# rev0_1.net
KiCad netlist of a schematic drawn in EAGLE
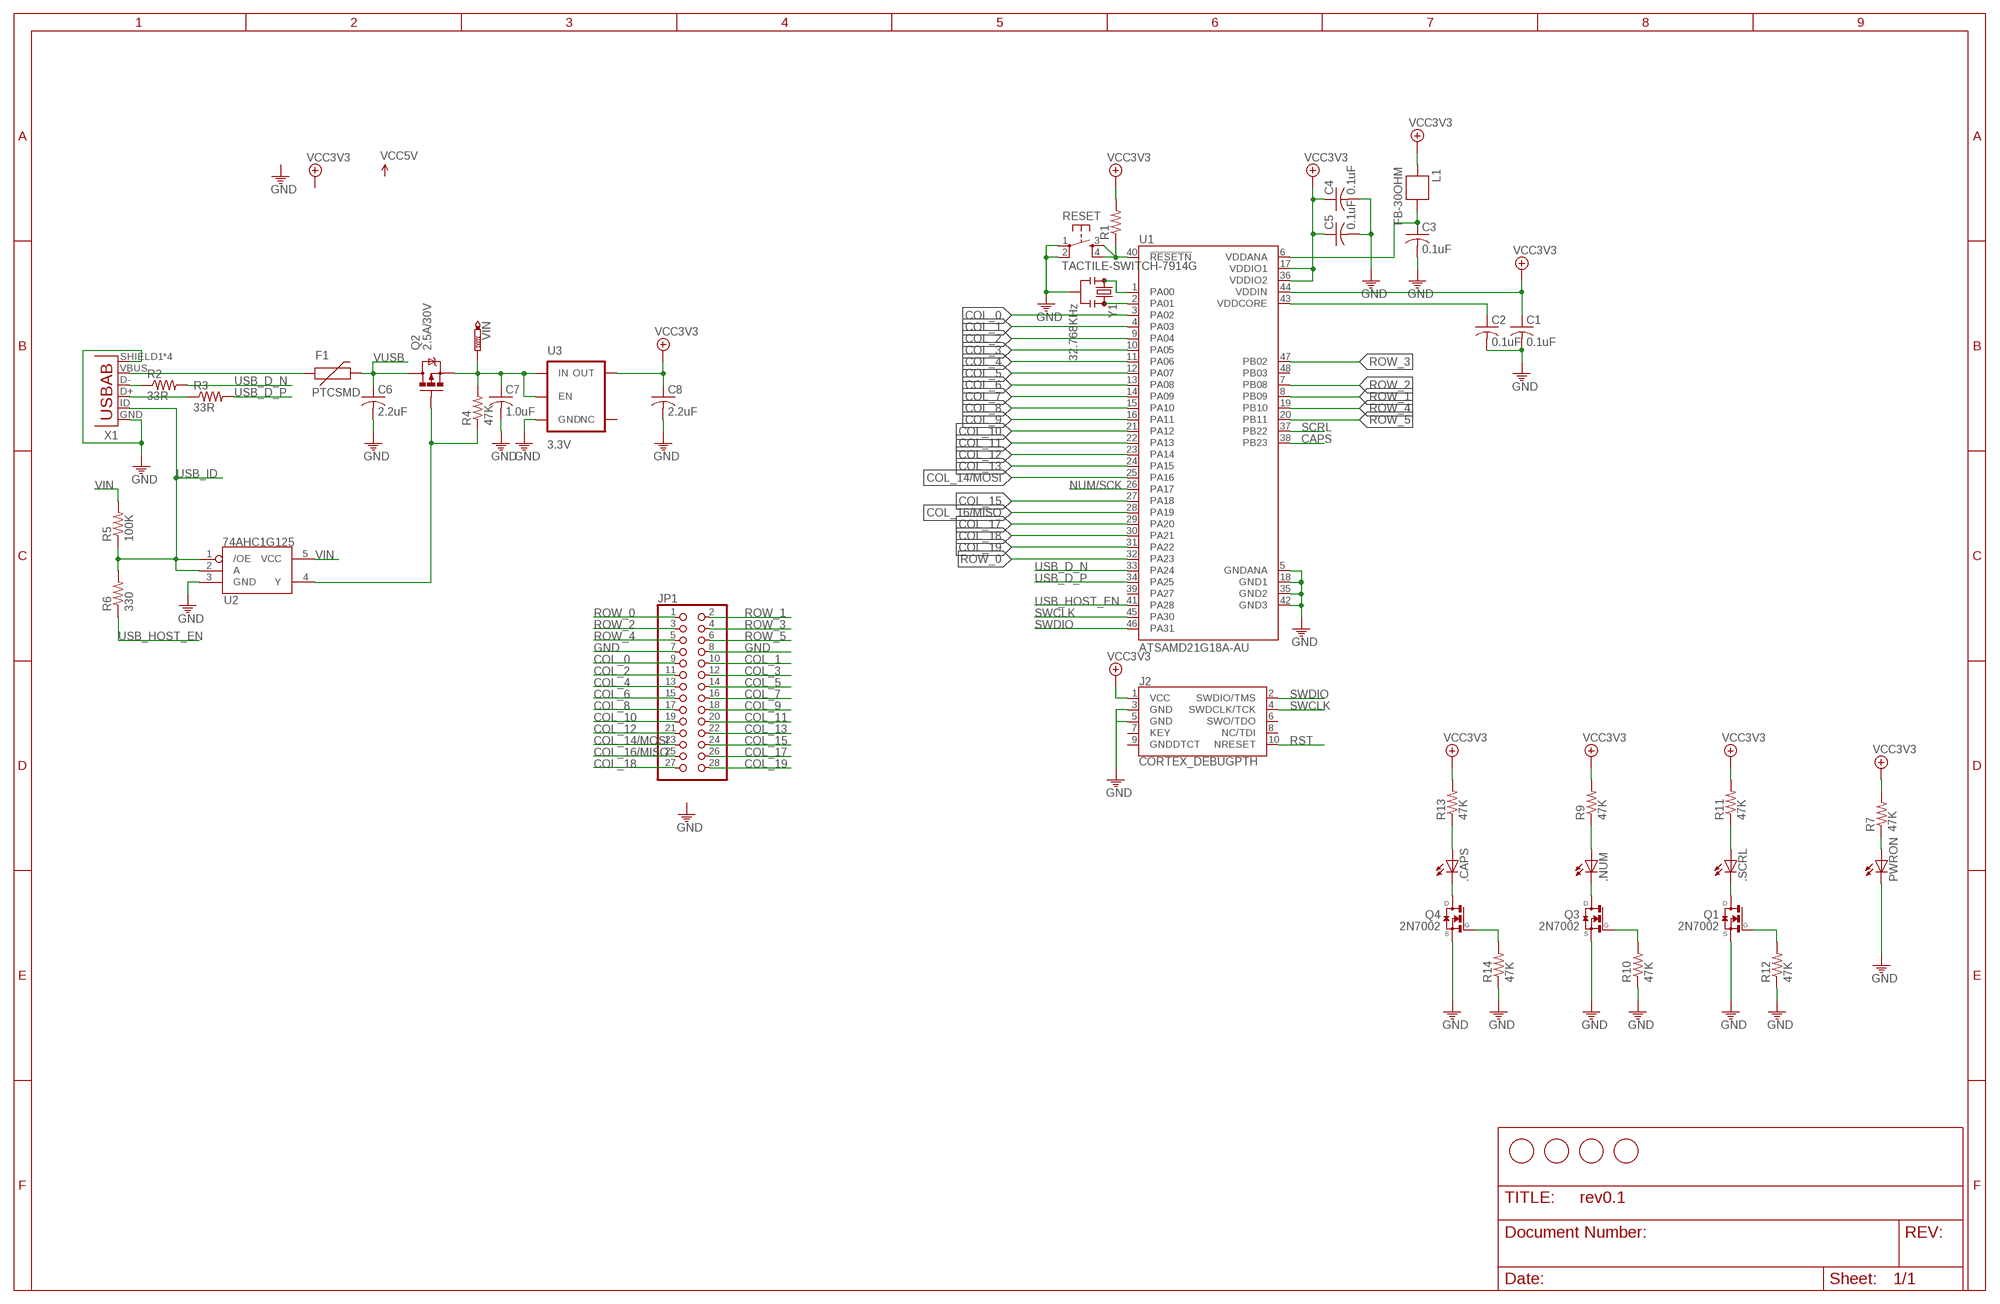
[diagram p0: schematic, sheet 1]

(export (version "E")
  (design (tool "Eeschema 10.0.6"))
  (components
    (comp (ref ".CAPS")
      (value "LEDCHIPLED_1206")
      (footprint "eagle-import:CHIPLED_1206")
      (libsource (lib "eagle-import") (part "LEDCHIPLED_1206"))
    )
    (comp (ref ".NUM")
      (value "LEDCHIPLED_1206")
      (footprint "eagle-import:CHIPLED_1206")
      (libsource (lib "eagle-import") (part "LEDCHIPLED_1206"))
    )
    (comp (ref ".SCRL")
      (value "LEDCHIPLED_1206")
      (footprint "eagle-import:CHIPLED_1206")
      (libsource (lib "eagle-import") (part "LEDCHIPLED_1206"))
    )
    (comp (ref "C1")
      (value "0.1uF")
      (footprint "eagle-import:C0603")
      (libsource (lib "eagle-import") (part "C-USC0603"))
    )
    (comp (ref "C2")
      (value "0.1uF")
      (footprint "eagle-import:C0603")
      (libsource (lib "eagle-import") (part "C-USC0603"))
    )
    (comp (ref "C3")
      (value "0.1uF")
      (footprint "eagle-import:C0603")
      (libsource (lib "eagle-import") (part "C-USC0603"))
    )
    (comp (ref "C4")
      (value "0.1uF")
      (footprint "eagle-import:C0603")
      (libsource (lib "eagle-import") (part "C-USC0603"))
    )
    (comp (ref "C5")
      (value "0.1uF")
      (footprint "eagle-import:C0603")
      (libsource (lib "eagle-import") (part "C-USC0603"))
    )
    (comp (ref "C6")
      (value "2.2uF")
      (footprint "eagle-import:C0603")
      (libsource (lib "eagle-import") (part "C-USC0603"))
    )
    (comp (ref "C7")
      (value "1.0uF")
      (footprint "eagle-import:C0603")
      (libsource (lib "eagle-import") (part "C-USC0603"))
    )
    (comp (ref "C8")
      (value "2.2uF")
      (footprint "eagle-import:C0603")
      (libsource (lib "eagle-import") (part "C-USC0603"))
    )
    (comp (ref "F1")
      (value "PTCSMD")
      (footprint "eagle-import:PTC-1206")
      (libsource (lib "eagle-import") (part "PTCSMD"))
    )
    (comp (ref "J2")
      (value "CORTEX_DEBUGPTH")
      (footprint "eagle-import:2X5-PTH-1.27MM")
      (libsource (lib "eagle-import") (part "CORTEX_DEBUGPTH"))
    )
    (comp (ref "JP1")
      (value "PINHD-2X14-CB")
      (footprint "eagle-import:2X14-CLEANBIG")
      (libsource (lib "eagle-import") (part "PINHD-2X14-CB"))
    )
    (comp (ref "L1")
      (value "FB-30OHM")
      (footprint "eagle-import:0603")
      (libsource (lib "eagle-import") (part "FB"))
    )
    (comp (ref "PWRON")
      (value "LEDCHIPLED_1206")
      (footprint "eagle-import:CHIPLED_1206")
      (libsource (lib "eagle-import") (part "LEDCHIPLED_1206"))
    )
    (comp (ref "Q1")
      (value "2N7002")
      (footprint "eagle-import:SOT23")
      (libsource (lib "eagle-import") (part "2N7002"))
    )
    (comp (ref "Q2")
      (value "2.5A/30V")
      (footprint "eagle-import:SOT23-3")
      (libsource (lib "eagle-import") (part "MOSFET-PCHANNELDMG2307L"))
    )
    (comp (ref "Q3")
      (value "2N7002")
      (footprint "eagle-import:SOT23")
      (libsource (lib "eagle-import") (part "2N7002"))
    )
    (comp (ref "Q4")
      (value "2N7002")
      (footprint "eagle-import:SOT23")
      (libsource (lib "eagle-import") (part "2N7002"))
    )
    (comp (ref "R1")
      (value "R-US_R0603")
      (footprint "eagle-import:R0603")
      (libsource (lib "eagle-import") (part "R-US_R0603"))
    )
    (comp (ref "R2")
      (value "33R")
      (footprint "eagle-import:R0603")
      (libsource (lib "eagle-import") (part "R-US_R0603"))
    )
    (comp (ref "R3")
      (value "33R")
      (footprint "eagle-import:R0603")
      (libsource (lib "eagle-import") (part "R-US_R0603"))
    )
    (comp (ref "R4")
      (value "47K")
      (footprint "eagle-import:R0603")
      (libsource (lib "eagle-import") (part "R-US_R0603"))
    )
    (comp (ref "R5")
      (value "100K")
      (footprint "eagle-import:R0603")
      (libsource (lib "eagle-import") (part "R-US_R0603"))
    )
    (comp (ref "R6")
      (value "330")
      (footprint "eagle-import:R0603")
      (libsource (lib "eagle-import") (part "R-US_R0603"))
    )
    (comp (ref "R7")
      (value "47K")
      (footprint "eagle-import:R0603")
      (libsource (lib "eagle-import") (part "R-US_R0603"))
    )
    (comp (ref "R9")
      (value "47K")
      (footprint "eagle-import:R0603")
      (libsource (lib "eagle-import") (part "R-US_R0603"))
    )
    (comp (ref "R10")
      (value "47K")
      (footprint "eagle-import:R0603")
      (libsource (lib "eagle-import") (part "R-US_R0603"))
    )
    (comp (ref "R11")
      (value "47K")
      (footprint "eagle-import:R0603")
      (libsource (lib "eagle-import") (part "R-US_R0603"))
    )
    (comp (ref "R12")
      (value "47K")
      (footprint "eagle-import:R0603")
      (libsource (lib "eagle-import") (part "R-US_R0603"))
    )
    (comp (ref "R13")
      (value "47K")
      (footprint "eagle-import:R0603")
      (libsource (lib "eagle-import") (part "R-US_R0603"))
    )
    (comp (ref "R14")
      (value "47K")
      (footprint "eagle-import:R0603")
      (libsource (lib "eagle-import") (part "R-US_R0603"))
    )
    (comp (ref "RESET")
      (value "TACTILE-SWITCH-7914G")
      (footprint "eagle-import:7914G")
      (libsource (lib "eagle-import") (part "TACTILE-SWITCH-7914G"))
    )
    (comp (ref "U$6")
      (value "FIDUCIAL")
      (footprint "eagle-import:FIDUCIAL_1MM")
      (libsource (lib "eagle-import") (part "FIDUCIAL"))
    )
    (comp (ref "U$19")
      (value "FIDUCIAL")
      (footprint "eagle-import:FIDUCIAL_1MM")
      (libsource (lib "eagle-import") (part "FIDUCIAL"))
    )
    (comp (ref "U$20")
      (value "FIDUCIAL")
      (footprint "eagle-import:FIDUCIAL_1MM")
      (libsource (lib "eagle-import") (part "FIDUCIAL"))
    )
    (comp (ref "U$21")
      (value "FIDUCIAL")
      (footprint "eagle-import:FIDUCIAL_1MM")
      (libsource (lib "eagle-import") (part "FIDUCIAL"))
    )
    (comp (ref "U1")
      (value "ATSAMD21G18A-AU")
      (footprint "eagle-import:QFP50P900X900X120-48N")
      (fields (field (name "MF") "Atmel"))
      (libsource (lib "eagle-import") (part "ATSAMD21G18A-AU"))
    )
    (comp (ref "U2")
      (value "74AHC1G125")
      (footprint "eagle-import:SOT23-5")
      (libsource (lib "eagle-import") (part "74AHC1G125"))
    )
    (comp (ref "U3")
      (value "3.3V")
      (footprint "eagle-import:SOT23-5")
      (libsource (lib "eagle-import") (part "V_REG_AP2112K-3.3V"))
    )
    (comp (ref "VIN")
      (value "PTR1PAD1-17")
      (footprint "eagle-import:P1-17")
      (libsource (lib "eagle-import") (part "PTR1PAD1-17"))
    )
    (comp (ref "X1")
      (value "USB-AB\"")
      (footprint "eagle-import:USB_AB_MICRO_1_1_V2")
      (libsource (lib "eagle-import") (part "USB-AB{dblquote}"))
    )
    (comp (ref "Y1")
      (value "32.768KHz")
      (footprint "eagle-import:RESONATOR-SMD")
      (libsource (lib "eagle-import") (part "RESONATOR16MHZ"))
    )
  )
  (nets
    (net (code "1") (name "/CAPS") (class "Default")
      (node (ref "Q4") (pin "1") (pinfunction "G_1") (pintype "passive"))
      (node (ref "R14") (pin "2") (pinfunction "2_2") (pintype "passive"))
      (node (ref "U1") (pin "38") (pinfunction "PB23_38") (pintype "bidirectional"))
    )
    (net (code "2") (name "/NUM{slash}SCK") (class "Default")
      (node (ref "Q3") (pin "1") (pinfunction "G_1") (pintype "passive"))
      (node (ref "R10") (pin "2") (pinfunction "2_2") (pintype "passive"))
      (node (ref "U1") (pin "26") (pinfunction "PA17_26") (pintype "bidirectional"))
    )
    (net (code "3") (name "/RST") (class "Default")
      (node (ref "J2") (pin "10") (pinfunction "NRESET_10") (pintype "bidirectional"))
      (node (ref "R1") (pin "1") (pinfunction "1_1") (pintype "passive"))
      (node (ref "RESET") (pin "3") (pinfunction "3_3") (pintype "passive"))
      (node (ref "RESET") (pin "4") (pinfunction "4_4") (pintype "passive"))
      (node (ref "U1") (pin "40") (pinfunction "~{RESETN}_40") (pintype "input"))
    )
    (net (code "4") (name "/SCRL") (class "Default")
      (node (ref "Q1") (pin "1") (pinfunction "G_1") (pintype "passive"))
      (node (ref "R12") (pin "2") (pinfunction "2_2") (pintype "passive"))
      (node (ref "U1") (pin "37") (pinfunction "PB22_37") (pintype "bidirectional"))
    )
    (net (code "5") (name "/SWCLK") (class "Default")
      (node (ref "J2") (pin "4") (pinfunction "SWDCLK/TCK_4") (pintype "bidirectional"))
      (node (ref "U1") (pin "45") (pinfunction "PA30_45") (pintype "bidirectional"))
    )
    (net (code "6") (name "/SWDIO") (class "Default")
      (node (ref "J2") (pin "2") (pinfunction "SWDIO/TMS_2") (pintype "bidirectional"))
      (node (ref "U1") (pin "46") (pinfunction "PA31_46") (pintype "bidirectional"))
    )
    (net (code "7") (name "/USB_D_N") (class "Default")
      (node (ref "R2") (pin "2") (pinfunction "2_2") (pintype "passive"))
      (node (ref "U1") (pin "33") (pinfunction "PA24_33") (pintype "bidirectional"))
    )
    (net (code "8") (name "/USB_D_P") (class "Default")
      (node (ref "R3") (pin "2") (pinfunction "2_2") (pintype "passive"))
      (node (ref "U1") (pin "34") (pinfunction "PA25_34") (pintype "bidirectional"))
    )
    (net (code "9") (name "/USB_HOST_EN") (class "Default")
      (node (ref "R6") (pin "1") (pinfunction "1_1") (pintype "passive"))
      (node (ref "U1") (pin "41") (pinfunction "PA28_41") (pintype "bidirectional"))
    )
    (net (code "10") (name "/USB_ID") (class "Default")
      (node (ref "R5") (pin "1") (pinfunction "1_1") (pintype "passive"))
      (node (ref "R6") (pin "2") (pinfunction "2_2") (pintype "passive"))
      (node (ref "U2") (pin "1") (pinfunction "/OE_1") (pintype "bidirectional"))
      (node (ref "U2") (pin "2") (pinfunction "A_2") (pintype "bidirectional"))
      (node (ref "X1") (pin "ID") (pinfunction "USBID_ID") (pintype "bidirectional"))
    )
    (net (code "11") (name "/VIN") (class "Default")
      (node (ref "C7") (pin "1") (pinfunction "1_1") (pintype "passive"))
      (node (ref "Q2") (pin "2") (pinfunction "S_2") (pintype "passive"))
      (node (ref "R4") (pin "2") (pinfunction "2_2") (pintype "passive"))
      (node (ref "R5") (pin "2") (pinfunction "2_2") (pintype "passive"))
      (node (ref "U2") (pin "5") (pinfunction "VCC_5") (pintype "bidirectional"))
      (node (ref "U3") (pin "1") (pinfunction "IN_1") (pintype "input"))
      (node (ref "U3") (pin "3") (pinfunction "EN_3") (pintype "input"))
      (node (ref "VIN") (pin "TP") (pinfunction "TP_TP") (pintype "input"))
    )
    (net (code "12") (name "/VUSB") (class "Default")
      (node (ref "C6") (pin "1") (pinfunction "1_1") (pintype "passive"))
      (node (ref "F1") (pin "2") (pinfunction "2_2") (pintype "bidirectional"))
      (node (ref "Q2") (pin "3") (pinfunction "D_3") (pintype "passive"))
    )
    (net (code "13") (name "COL_0") (class "Default")
      (node (ref "JP1") (pin "9") (pinfunction "9_9") (pintype "passive"))
      (node (ref "U1") (pin "3") (pinfunction "PA02_3") (pintype "bidirectional"))
    )
    (net (code "14") (name "COL_1") (class "Default")
      (node (ref "JP1") (pin "10") (pinfunction "10_10") (pintype "passive"))
      (node (ref "U1") (pin "4") (pinfunction "PA03_4") (pintype "bidirectional"))
    )
    (net (code "15") (name "COL_2") (class "Default")
      (node (ref "JP1") (pin "11") (pinfunction "11_11") (pintype "passive"))
      (node (ref "U1") (pin "9") (pinfunction "PA04_9") (pintype "bidirectional"))
    )
    (net (code "16") (name "COL_3") (class "Default")
      (node (ref "JP1") (pin "12") (pinfunction "12_12") (pintype "passive"))
      (node (ref "U1") (pin "10") (pinfunction "PA05_10") (pintype "bidirectional"))
    )
    (net (code "17") (name "COL_4") (class "Default")
      (node (ref "JP1") (pin "13") (pinfunction "13_13") (pintype "passive"))
      (node (ref "U1") (pin "11") (pinfunction "PA06_11") (pintype "bidirectional"))
    )
    (net (code "18") (name "COL_5") (class "Default")
      (node (ref "JP1") (pin "14") (pinfunction "14_14") (pintype "passive"))
      (node (ref "U1") (pin "12") (pinfunction "PA07_12") (pintype "bidirectional"))
    )
    (net (code "19") (name "COL_6") (class "Default")
      (node (ref "JP1") (pin "15") (pinfunction "15_15") (pintype "passive"))
      (node (ref "U1") (pin "13") (pinfunction "PA08_13") (pintype "bidirectional"))
    )
    (net (code "20") (name "COL_7") (class "Default")
      (node (ref "JP1") (pin "16") (pinfunction "16_16") (pintype "passive"))
      (node (ref "U1") (pin "14") (pinfunction "PA09_14") (pintype "bidirectional"))
    )
    (net (code "21") (name "COL_8") (class "Default")
      (node (ref "JP1") (pin "17") (pinfunction "17_17") (pintype "passive"))
      (node (ref "U1") (pin "15") (pinfunction "PA10_15") (pintype "bidirectional"))
    )
    (net (code "22") (name "COL_9") (class "Default")
      (node (ref "JP1") (pin "18") (pinfunction "18_18") (pintype "passive"))
      (node (ref "U1") (pin "16") (pinfunction "PA11_16") (pintype "bidirectional"))
    )
    (net (code "23") (name "COL_10") (class "Default")
      (node (ref "JP1") (pin "19") (pinfunction "19_19") (pintype "passive"))
      (node (ref "U1") (pin "21") (pinfunction "PA12_21") (pintype "bidirectional"))
    )
    (net (code "24") (name "COL_11") (class "Default")
      (node (ref "JP1") (pin "20") (pinfunction "20_20") (pintype "passive"))
      (node (ref "U1") (pin "22") (pinfunction "PA13_22") (pintype "bidirectional"))
    )
    (net (code "25") (name "COL_12") (class "Default")
      (node (ref "JP1") (pin "21") (pinfunction "21_21") (pintype "passive"))
      (node (ref "U1") (pin "23") (pinfunction "PA14_23") (pintype "bidirectional"))
    )
    (net (code "26") (name "COL_13") (class "Default")
      (node (ref "JP1") (pin "22") (pinfunction "22_22") (pintype "passive"))
      (node (ref "U1") (pin "24") (pinfunction "PA15_24") (pintype "bidirectional"))
    )
    (net (code "27") (name "COL_14{slash}MOSI") (class "Default")
      (node (ref "JP1") (pin "23") (pinfunction "23_23") (pintype "passive"))
      (node (ref "U1") (pin "25") (pinfunction "PA16_25") (pintype "bidirectional"))
    )
    (net (code "28") (name "COL_15") (class "Default")
      (node (ref "JP1") (pin "24") (pinfunction "24_24") (pintype "passive"))
      (node (ref "U1") (pin "27") (pinfunction "PA18_27") (pintype "bidirectional"))
    )
    (net (code "29") (name "COL_16{slash}MISO") (class "Default")
      (node (ref "JP1") (pin "25") (pinfunction "25_25") (pintype "passive"))
      (node (ref "U1") (pin "28") (pinfunction "PA19_28") (pintype "bidirectional"))
    )
    (net (code "30") (name "COL_17") (class "Default")
      (node (ref "JP1") (pin "26") (pinfunction "26_26") (pintype "passive"))
      (node (ref "U1") (pin "29") (pinfunction "PA20_29") (pintype "bidirectional"))
    )
    (net (code "31") (name "COL_18") (class "Default")
      (node (ref "JP1") (pin "27") (pinfunction "27_27") (pintype "passive"))
      (node (ref "U1") (pin "30") (pinfunction "PA21_30") (pintype "bidirectional"))
    )
    (net (code "32") (name "COL_19") (class "Default")
      (node (ref "JP1") (pin "28") (pinfunction "28_28") (pintype "passive"))
      (node (ref "U1") (pin "31") (pinfunction "PA22_31") (pintype "bidirectional"))
    )
    (net (code "33") (name "GND") (class "Default")
      (node (ref "C1") (pin "2") (pinfunction "2_2") (pintype "passive"))
      (node (ref "C2") (pin "2") (pinfunction "2_2") (pintype "passive"))
      (node (ref "C3") (pin "2") (pinfunction "2_2") (pintype "passive"))
      (node (ref "C4") (pin "2") (pinfunction "2_2") (pintype "passive"))
      (node (ref "C5") (pin "2") (pinfunction "2_2") (pintype "passive"))
      (node (ref "C6") (pin "2") (pinfunction "2_2") (pintype "passive"))
      (node (ref "C7") (pin "2") (pinfunction "2_2") (pintype "passive"))
      (node (ref "C8") (pin "2") (pinfunction "2_2") (pintype "passive"))
      (node (ref "J2") (pin "3") (pinfunction "GND_3") (pintype "bidirectional"))
      (node (ref "J2") (pin "5") (pinfunction "GND_5") (pintype "bidirectional"))
      (node (ref "JP1") (pin "7") (pinfunction "7_7") (pintype "passive"))
      (node (ref "JP1") (pin "8") (pinfunction "8_8") (pintype "passive"))
      (node (ref "PWRON") (pin "C") (pinfunction "C_C") (pintype "passive"))
      (node (ref "Q1") (pin "2") (pinfunction "S_2") (pintype "passive"))
      (node (ref "Q3") (pin "2") (pinfunction "S_2") (pintype "passive"))
      (node (ref "Q4") (pin "2") (pinfunction "S_2") (pintype "passive"))
      (node (ref "R10") (pin "1") (pinfunction "1_1") (pintype "passive"))
      (node (ref "R12") (pin "1") (pinfunction "1_1") (pintype "passive"))
      (node (ref "R14") (pin "1") (pinfunction "1_1") (pintype "passive"))
      (node (ref "RESET") (pin "1") (pinfunction "1_1") (pintype "passive"))
      (node (ref "RESET") (pin "2") (pinfunction "2_2") (pintype "passive"))
      (node (ref "U1") (pin "18") (pinfunction "GND1_18") (pintype "power_in"))
      (node (ref "U1") (pin "35") (pinfunction "GND2_35") (pintype "power_in"))
      (node (ref "U1") (pin "42") (pinfunction "GND3_42") (pintype "power_in"))
      (node (ref "U1") (pin "5") (pinfunction "GNDANA_5") (pintype "power_in"))
      (node (ref "U2") (pin "3") (pinfunction "GND_3") (pintype "bidirectional"))
      (node (ref "U3") (pin "2") (pinfunction "GND_2") (pintype "input"))
      (node (ref "X1") (pin "GND") (pinfunction "GND_GND") (pintype "bidirectional"))
      (node (ref "X1") (pin "SHIELD1") (pinfunction "SHIELD_SHIELD1") (pintype "bidirectional"))
      (node (ref "X1") (pin "SHIELD2") (pinfunction "SHIELD_SHIELD2") (pintype "bidirectional"))
      (node (ref "X1") (pin "SHIELD3") (pinfunction "SHIELD_SHIELD3") (pintype "bidirectional"))
      (node (ref "X1") (pin "SHIELD4") (pinfunction "SHIELD_SHIELD4") (pintype "bidirectional"))
      (node (ref "Y1") (pin "2") (pinfunction "2_2") (pintype "passive"))
    )
    (net (code "34") (name "Net-(.CAPS-PadA)") (class "Default")
      (node (ref ".CAPS") (pin "A") (pinfunction "A_A") (pintype "passive"))
      (node (ref "R13") (pin "1") (pinfunction "1_1") (pintype "passive"))
    )
    (net (code "35") (name "Net-(.NUM-PadA)") (class "Default")
      (node (ref ".NUM") (pin "A") (pinfunction "A_A") (pintype "passive"))
      (node (ref "R9") (pin "1") (pinfunction "1_1") (pintype "passive"))
    )
    (net (code "36") (name "Net-(.SCRL-PadA)") (class "Default")
      (node (ref ".SCRL") (pin "A") (pinfunction "A_A") (pintype "passive"))
      (node (ref "R11") (pin "1") (pinfunction "1_1") (pintype "passive"))
    )
    (net (code "37") (name "Net-(F1-Pad1)") (class "Default")
      (node (ref "F1") (pin "1") (pinfunction "1_1") (pintype "bidirectional"))
      (node (ref "X1") (pin "VBUS") (pinfunction "VBUS_VBUS") (pintype "bidirectional"))
    )
    (net (code "38") (name "Net-(L1-P$1)") (class "Default")
      (node (ref "C3") (pin "1") (pinfunction "1_1") (pintype "passive"))
      (node (ref "L1") (pin "1") (pinfunction "P$1_1") (pintype "bidirectional"))
      (node (ref "U1") (pin "6") (pinfunction "VDDANA_6") (pintype "power_in"))
    )
    (net (code "39") (name "Net-(PWRON-PadA)") (class "Default")
      (node (ref "PWRON") (pin "A") (pinfunction "A_A") (pintype "passive"))
      (node (ref "R7") (pin "1") (pinfunction "1_1") (pintype "passive"))
    )
    (net (code "40") (name "Net-(Q1-D)") (class "Default")
      (node (ref ".SCRL") (pin "C") (pinfunction "C_C") (pintype "passive"))
      (node (ref "Q1") (pin "3") (pinfunction "D_3") (pintype "passive"))
    )
    (net (code "41") (name "Net-(Q2-G)") (class "Default")
      (node (ref "Q2") (pin "1") (pinfunction "G_1") (pintype "passive"))
      (node (ref "R4") (pin "1") (pinfunction "1_1") (pintype "passive"))
      (node (ref "U2") (pin "4") (pinfunction "Y_4") (pintype "bidirectional"))
    )
    (net (code "42") (name "Net-(Q3-D)") (class "Default")
      (node (ref ".NUM") (pin "C") (pinfunction "C_C") (pintype "passive"))
      (node (ref "Q3") (pin "3") (pinfunction "D_3") (pintype "passive"))
    )
    (net (code "43") (name "Net-(Q4-D)") (class "Default")
      (node (ref ".CAPS") (pin "C") (pinfunction "C_C") (pintype "passive"))
      (node (ref "Q4") (pin "3") (pinfunction "D_3") (pintype "passive"))
    )
    (net (code "44") (name "Net-(R2-Pad1)") (class "Default")
      (node (ref "R2") (pin "1") (pinfunction "1_1") (pintype "passive"))
      (node (ref "X1") (pin "D-") (pinfunction "D-_D-") (pintype "bidirectional"))
    )
    (net (code "45") (name "Net-(R3-Pad1)") (class "Default")
      (node (ref "R3") (pin "1") (pinfunction "1_1") (pintype "passive"))
      (node (ref "X1") (pin "D+") (pinfunction "D+_D+") (pintype "bidirectional"))
    )
    (net (code "46") (name "Net-(U1-PA00)") (class "Default")
      (node (ref "U1") (pin "1") (pinfunction "PA00_1") (pintype "bidirectional"))
      (node (ref "Y1") (pin "1") (pinfunction "1_1") (pintype "passive"))
    )
    (net (code "47") (name "Net-(U1-PA01)") (class "Default")
      (node (ref "U1") (pin "2") (pinfunction "PA01_2") (pintype "bidirectional"))
      (node (ref "Y1") (pin "3") (pinfunction "3_3") (pintype "passive"))
    )
    (net (code "48") (name "Net-(U1-VDDCORE)") (class "Default")
      (node (ref "C2") (pin "1") (pinfunction "1_1") (pintype "passive"))
      (node (ref "U1") (pin "43") (pinfunction "VDDCORE_43") (pintype "power_in"))
    )
    (net (code "49") (name "ROW_0") (class "Default")
      (node (ref "JP1") (pin "1") (pinfunction "1_1") (pintype "passive"))
      (node (ref "U1") (pin "32") (pinfunction "PA23_32") (pintype "bidirectional"))
    )
    (net (code "50") (name "ROW_1") (class "Default")
      (node (ref "JP1") (pin "2") (pinfunction "2_2") (pintype "passive"))
      (node (ref "U1") (pin "8") (pinfunction "PB09_8") (pintype "bidirectional"))
    )
    (net (code "51") (name "ROW_2") (class "Default")
      (node (ref "JP1") (pin "3") (pinfunction "3_3") (pintype "passive"))
      (node (ref "U1") (pin "7") (pinfunction "PB08_7") (pintype "bidirectional"))
    )
    (net (code "52") (name "ROW_3") (class "Default")
      (node (ref "JP1") (pin "4") (pinfunction "4_4") (pintype "passive"))
      (node (ref "U1") (pin "47") (pinfunction "PB02_47") (pintype "bidirectional"))
    )
    (net (code "53") (name "ROW_4") (class "Default")
      (node (ref "JP1") (pin "5") (pinfunction "5_5") (pintype "passive"))
      (node (ref "U1") (pin "19") (pinfunction "PB10_19") (pintype "bidirectional"))
    )
    (net (code "54") (name "ROW_5") (class "Default")
      (node (ref "JP1") (pin "6") (pinfunction "6_6") (pintype "passive"))
      (node (ref "U1") (pin "20") (pinfunction "PB11_20") (pintype "bidirectional"))
    )
    (net (code "55") (name "VCC3V3") (class "Default")
      (node (ref "C1") (pin "1") (pinfunction "1_1") (pintype "passive"))
      (node (ref "C4") (pin "1") (pinfunction "1_1") (pintype "passive"))
      (node (ref "C5") (pin "1") (pinfunction "1_1") (pintype "passive"))
      (node (ref "C8") (pin "1") (pinfunction "1_1") (pintype "passive"))
      (node (ref "J2") (pin "1") (pinfunction "VCC_1") (pintype "bidirectional"))
      (node (ref "L1") (pin "2") (pinfunction "P$2_2") (pintype "bidirectional"))
      (node (ref "R1") (pin "2") (pinfunction "2_2") (pintype "passive"))
      (node (ref "R11") (pin "2") (pinfunction "2_2") (pintype "passive"))
      (node (ref "R13") (pin "2") (pinfunction "2_2") (pintype "passive"))
      (node (ref "R7") (pin "2") (pinfunction "2_2") (pintype "passive"))
      (node (ref "R9") (pin "2") (pinfunction "2_2") (pintype "passive"))
      (node (ref "U1") (pin "17") (pinfunction "VDDIO1_17") (pintype "power_in"))
      (node (ref "U1") (pin "36") (pinfunction "VDDIO2_36") (pintype "power_in"))
      (node (ref "U1") (pin "44") (pinfunction "VDDIN_44") (pintype "power_in"))
      (node (ref "U3") (pin "5") (pinfunction "OUT_5") (pintype "passive"))
    )
    (net (code "57") (name "unconnected-(J2-GNDDTCT-Pad9)") (class "Default")
      (node (ref "J2") (pin "9") (pinfunction "GNDDTCT_9") (pintype "bidirectional"))
    )
    (net (code "58") (name "unconnected-(J2-KEY-Pad7)") (class "Default")
      (node (ref "J2") (pin "7") (pinfunction "KEY_7") (pintype "bidirectional"))
    )
    (net (code "59") (name "unconnected-(J2-NC{slash}TDI-Pad8)") (class "Default")
      (node (ref "J2") (pin "8") (pinfunction "NC/TDI_8") (pintype "bidirectional"))
    )
    (net (code "60") (name "unconnected-(J2-SWO{slash}TDO-Pad6)") (class "Default")
      (node (ref "J2") (pin "6") (pinfunction "SWO/TDO_6") (pintype "bidirectional"))
    )
    (net (code "61") (name "unconnected-(U1-PA27-Pad39)") (class "Default")
      (node (ref "U1") (pin "39") (pinfunction "PA27_39") (pintype "bidirectional"))
    )
    (net (code "62") (name "unconnected-(U1-PB03-Pad48)") (class "Default")
      (node (ref "U1") (pin "48") (pinfunction "PB03_48") (pintype "bidirectional"))
    )
    (net (code "63") (name "unconnected-(U3-NC-Pad4)") (class "Default")
      (node (ref "U3") (pin "4") (pinfunction "NC_4") (pintype "input"))
    )
  )
)
